# LED_DRIVER.net
KiCad netlist of a schematic drawn in EAGLE
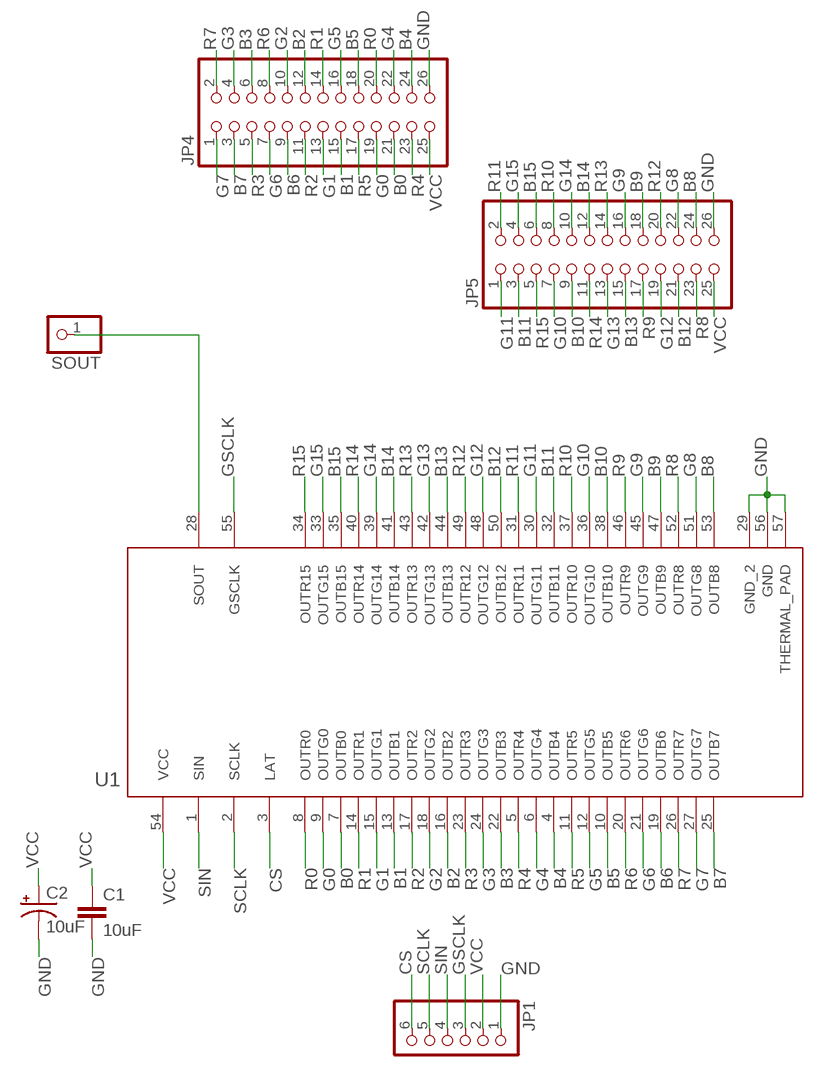
[diagram p0: schematic, sheet 1]

(export (version "E")
  (design (tool "Eeschema 10.0.6"))
  (components
    (comp (ref "C1")
      (value "10uF")
      (footprint "eagle-import:C0603")
      (libsource (lib "eagle-import") (part "C-EUC0603"))
    )
    (comp (ref "C2")
      (value "10uF")
      (footprint "eagle-import:E2-4")
      (libsource (lib "eagle-import") (part "CPOL-USE2-4"))
    )
    (comp (ref "JP1")
      (value "PINHD-1X6")
      (footprint "eagle-import:1X06")
      (libsource (lib "eagle-import") (part "PINHD-1X6"))
    )
    (comp (ref "JP4")
      (value "PINHD-2X13")
      (footprint "eagle-import:2X13")
      (libsource (lib "eagle-import") (part "PINHD-2X13"))
    )
    (comp (ref "JP5")
      (value "PINHD-2X13")
      (footprint "eagle-import:2X13")
      (libsource (lib "eagle-import") (part "PINHD-2X13"))
    )
    (comp (ref "SOUT")
      (value "PINHD-1X1")
      (footprint "eagle-import:1X01")
      (libsource (lib "eagle-import") (part "PINHD-1X1"))
    )
    (comp (ref "U1")
      (value "Value")
      (footprint "eagle-import:DCA0056F-IPC_B")
      (fields
        (field (name "MANUFACTURER") "Texas Instruments")
        (field (name "PARTNUMBER") "TLC6C5748QDCARQ1")
      )
      (libsource (lib "eagle-import") (part "TLC6C5748QDCARQ1DCA0056F-IPC_B"))
    )
  )
  (nets
    (net (code "1") (name "/B0") (class "Default")
      (node (ref "JP4") (pin "21") (pinfunction "21_21") (pintype "passive"))
      (node (ref "U1") (pin "7") (pinfunction "OUTB0_7") (pintype "output"))
    )
    (net (code "2") (name "/B1") (class "Default")
      (node (ref "JP4") (pin "15") (pinfunction "15_15") (pintype "passive"))
      (node (ref "U1") (pin "13") (pinfunction "OUTB1_13") (pintype "output"))
    )
    (net (code "3") (name "/B2") (class "Default")
      (node (ref "JP4") (pin "12") (pinfunction "12_12") (pintype "passive"))
      (node (ref "U1") (pin "16") (pinfunction "OUTB2_16") (pintype "output"))
    )
    (net (code "4") (name "/B3") (class "Default")
      (node (ref "JP4") (pin "6") (pinfunction "6_6") (pintype "passive"))
      (node (ref "U1") (pin "22") (pinfunction "OUTB3_22") (pintype "output"))
    )
    (net (code "5") (name "/B4") (class "Default")
      (node (ref "JP4") (pin "24") (pinfunction "24_24") (pintype "passive"))
      (node (ref "U1") (pin "4") (pinfunction "OUTB4_4") (pintype "output"))
    )
    (net (code "6") (name "/B5") (class "Default")
      (node (ref "JP4") (pin "18") (pinfunction "18_18") (pintype "passive"))
      (node (ref "U1") (pin "10") (pinfunction "OUTB5_10") (pintype "output"))
    )
    (net (code "7") (name "/B6") (class "Default")
      (node (ref "JP4") (pin "9") (pinfunction "9_9") (pintype "passive"))
      (node (ref "U1") (pin "19") (pinfunction "OUTB6_19") (pintype "output"))
    )
    (net (code "8") (name "/B7") (class "Default")
      (node (ref "JP4") (pin "3") (pinfunction "3_3") (pintype "passive"))
      (node (ref "U1") (pin "25") (pinfunction "OUTB7_25") (pintype "output"))
    )
    (net (code "9") (name "/B8") (class "Default")
      (node (ref "JP5") (pin "24") (pinfunction "24_24") (pintype "passive"))
      (node (ref "U1") (pin "53") (pinfunction "OUTB8_53") (pintype "output"))
    )
    (net (code "10") (name "/B9") (class "Default")
      (node (ref "JP5") (pin "18") (pinfunction "18_18") (pintype "passive"))
      (node (ref "U1") (pin "47") (pinfunction "OUTB9_47") (pintype "output"))
    )
    (net (code "11") (name "/B10") (class "Default")
      (node (ref "JP5") (pin "9") (pinfunction "9_9") (pintype "passive"))
      (node (ref "U1") (pin "38") (pinfunction "OUTB10_38") (pintype "output"))
    )
    (net (code "12") (name "/B11") (class "Default")
      (node (ref "JP5") (pin "3") (pinfunction "3_3") (pintype "passive"))
      (node (ref "U1") (pin "32") (pinfunction "OUTB11_32") (pintype "output"))
    )
    (net (code "13") (name "/B12") (class "Default")
      (node (ref "JP5") (pin "21") (pinfunction "21_21") (pintype "passive"))
      (node (ref "U1") (pin "50") (pinfunction "OUTB12_50") (pintype "output"))
    )
    (net (code "14") (name "/B13") (class "Default")
      (node (ref "JP5") (pin "15") (pinfunction "15_15") (pintype "passive"))
      (node (ref "U1") (pin "44") (pinfunction "OUTB13_44") (pintype "output"))
    )
    (net (code "15") (name "/B14") (class "Default")
      (node (ref "JP5") (pin "12") (pinfunction "12_12") (pintype "passive"))
      (node (ref "U1") (pin "41") (pinfunction "OUTB14_41") (pintype "output"))
    )
    (net (code "16") (name "/B15") (class "Default")
      (node (ref "JP5") (pin "6") (pinfunction "6_6") (pintype "passive"))
      (node (ref "U1") (pin "35") (pinfunction "OUTB15_35") (pintype "output"))
    )
    (net (code "17") (name "/CS") (class "Default")
      (node (ref "JP1") (pin "6") (pinfunction "6_6") (pintype "passive"))
      (node (ref "U1") (pin "3") (pinfunction "LAT_3") (pintype "input"))
    )
    (net (code "18") (name "/G0") (class "Default")
      (node (ref "JP4") (pin "19") (pinfunction "19_19") (pintype "passive"))
      (node (ref "U1") (pin "9") (pinfunction "OUTG0_9") (pintype "output"))
    )
    (net (code "19") (name "/G1") (class "Default")
      (node (ref "JP4") (pin "13") (pinfunction "13_13") (pintype "passive"))
      (node (ref "U1") (pin "15") (pinfunction "OUTG1_15") (pintype "output"))
    )
    (net (code "20") (name "/G2") (class "Default")
      (node (ref "JP4") (pin "10") (pinfunction "10_10") (pintype "passive"))
      (node (ref "U1") (pin "18") (pinfunction "OUTG2_18") (pintype "output"))
    )
    (net (code "21") (name "/G3") (class "Default")
      (node (ref "JP4") (pin "4") (pinfunction "4_4") (pintype "passive"))
      (node (ref "U1") (pin "24") (pinfunction "OUTG3_24") (pintype "output"))
    )
    (net (code "22") (name "/G4") (class "Default")
      (node (ref "JP4") (pin "22") (pinfunction "22_22") (pintype "passive"))
      (node (ref "U1") (pin "6") (pinfunction "OUTG4_6") (pintype "output"))
    )
    (net (code "23") (name "/G5") (class "Default")
      (node (ref "JP4") (pin "16") (pinfunction "16_16") (pintype "passive"))
      (node (ref "U1") (pin "12") (pinfunction "OUTG5_12") (pintype "output"))
    )
    (net (code "24") (name "/G6") (class "Default")
      (node (ref "JP4") (pin "7") (pinfunction "7_7") (pintype "passive"))
      (node (ref "U1") (pin "21") (pinfunction "OUTG6_21") (pintype "output"))
    )
    (net (code "25") (name "/G7") (class "Default")
      (node (ref "JP4") (pin "1") (pinfunction "1_1") (pintype "passive"))
      (node (ref "U1") (pin "27") (pinfunction "OUTG7_27") (pintype "output"))
    )
    (net (code "26") (name "/G8") (class "Default")
      (node (ref "JP5") (pin "22") (pinfunction "22_22") (pintype "passive"))
      (node (ref "U1") (pin "51") (pinfunction "OUTG8_51") (pintype "output"))
    )
    (net (code "27") (name "/G9") (class "Default")
      (node (ref "JP5") (pin "16") (pinfunction "16_16") (pintype "passive"))
      (node (ref "U1") (pin "45") (pinfunction "OUTG9_45") (pintype "output"))
    )
    (net (code "28") (name "/G10") (class "Default")
      (node (ref "JP5") (pin "7") (pinfunction "7_7") (pintype "passive"))
      (node (ref "U1") (pin "36") (pinfunction "OUTG10_36") (pintype "output"))
    )
    (net (code "29") (name "/G11") (class "Default")
      (node (ref "JP5") (pin "1") (pinfunction "1_1") (pintype "passive"))
      (node (ref "U1") (pin "30") (pinfunction "OUTG11_30") (pintype "output"))
    )
    (net (code "30") (name "/G12") (class "Default")
      (node (ref "JP5") (pin "19") (pinfunction "19_19") (pintype "passive"))
      (node (ref "U1") (pin "48") (pinfunction "OUTG12_48") (pintype "output"))
    )
    (net (code "31") (name "/G13") (class "Default")
      (node (ref "JP5") (pin "13") (pinfunction "13_13") (pintype "passive"))
      (node (ref "U1") (pin "42") (pinfunction "OUTG13_42") (pintype "output"))
    )
    (net (code "32") (name "/G14") (class "Default")
      (node (ref "JP5") (pin "10") (pinfunction "10_10") (pintype "passive"))
      (node (ref "U1") (pin "39") (pinfunction "OUTG14_39") (pintype "output"))
    )
    (net (code "33") (name "/G15") (class "Default")
      (node (ref "JP5") (pin "4") (pinfunction "4_4") (pintype "passive"))
      (node (ref "U1") (pin "33") (pinfunction "OUTG15_33") (pintype "output"))
    )
    (net (code "34") (name "/GND") (class "Default")
      (node (ref "C1") (pin "2") (pinfunction "2_2") (pintype "passive"))
      (node (ref "C2") (pin "-") (pinfunction "-_-") (pintype "passive"))
      (node (ref "JP1") (pin "1") (pinfunction "1_1") (pintype "passive"))
      (node (ref "JP4") (pin "26") (pinfunction "26_26") (pintype "passive"))
      (node (ref "JP5") (pin "26") (pinfunction "26_26") (pintype "passive"))
      (node (ref "U1") (pin "29") (pinfunction "GND_2_29") (pintype "power_in"))
      (node (ref "U1") (pin "56") (pinfunction "GND_56") (pintype "power_in"))
      (node (ref "U1") (pin "57") (pinfunction "THERMAL_PAD_57") (pintype "passive"))
    )
    (net (code "35") (name "/GSCLK") (class "Default")
      (node (ref "JP1") (pin "3") (pinfunction "3_3") (pintype "passive"))
      (node (ref "U1") (pin "55") (pinfunction "GSCLK_55") (pintype "input"))
    )
    (net (code "36") (name "/R0") (class "Default")
      (node (ref "JP4") (pin "20") (pinfunction "20_20") (pintype "passive"))
      (node (ref "U1") (pin "8") (pinfunction "OUTR0_8") (pintype "output"))
    )
    (net (code "37") (name "/R1") (class "Default")
      (node (ref "JP4") (pin "14") (pinfunction "14_14") (pintype "passive"))
      (node (ref "U1") (pin "14") (pinfunction "OUTR1_14") (pintype "output"))
    )
    (net (code "38") (name "/R2") (class "Default")
      (node (ref "JP4") (pin "11") (pinfunction "11_11") (pintype "passive"))
      (node (ref "U1") (pin "17") (pinfunction "OUTR2_17") (pintype "output"))
    )
    (net (code "39") (name "/R3") (class "Default")
      (node (ref "JP4") (pin "5") (pinfunction "5_5") (pintype "passive"))
      (node (ref "U1") (pin "23") (pinfunction "OUTR3_23") (pintype "output"))
    )
    (net (code "40") (name "/R4") (class "Default")
      (node (ref "JP4") (pin "23") (pinfunction "23_23") (pintype "passive"))
      (node (ref "U1") (pin "5") (pinfunction "OUTR4_5") (pintype "output"))
    )
    (net (code "41") (name "/R5") (class "Default")
      (node (ref "JP4") (pin "17") (pinfunction "17_17") (pintype "passive"))
      (node (ref "U1") (pin "11") (pinfunction "OUTR5_11") (pintype "output"))
    )
    (net (code "42") (name "/R6") (class "Default")
      (node (ref "JP4") (pin "8") (pinfunction "8_8") (pintype "passive"))
      (node (ref "U1") (pin "20") (pinfunction "OUTR6_20") (pintype "output"))
    )
    (net (code "43") (name "/R7") (class "Default")
      (node (ref "JP4") (pin "2") (pinfunction "2_2") (pintype "passive"))
      (node (ref "U1") (pin "26") (pinfunction "OUTR7_26") (pintype "output"))
    )
    (net (code "44") (name "/R8") (class "Default")
      (node (ref "JP5") (pin "23") (pinfunction "23_23") (pintype "passive"))
      (node (ref "U1") (pin "52") (pinfunction "OUTR8_52") (pintype "output"))
    )
    (net (code "45") (name "/R9") (class "Default")
      (node (ref "JP5") (pin "17") (pinfunction "17_17") (pintype "passive"))
      (node (ref "U1") (pin "46") (pinfunction "OUTR9_46") (pintype "output"))
    )
    (net (code "46") (name "/R10") (class "Default")
      (node (ref "JP5") (pin "8") (pinfunction "8_8") (pintype "passive"))
      (node (ref "U1") (pin "37") (pinfunction "OUTR10_37") (pintype "output"))
    )
    (net (code "47") (name "/R11") (class "Default")
      (node (ref "JP5") (pin "2") (pinfunction "2_2") (pintype "passive"))
      (node (ref "U1") (pin "31") (pinfunction "OUTR11_31") (pintype "output"))
    )
    (net (code "48") (name "/R12") (class "Default")
      (node (ref "JP5") (pin "20") (pinfunction "20_20") (pintype "passive"))
      (node (ref "U1") (pin "49") (pinfunction "OUTR12_49") (pintype "output"))
    )
    (net (code "49") (name "/R13") (class "Default")
      (node (ref "JP5") (pin "14") (pinfunction "14_14") (pintype "passive"))
      (node (ref "U1") (pin "43") (pinfunction "OUTR13_43") (pintype "output"))
    )
    (net (code "50") (name "/R14") (class "Default")
      (node (ref "JP5") (pin "11") (pinfunction "11_11") (pintype "passive"))
      (node (ref "U1") (pin "40") (pinfunction "OUTR14_40") (pintype "output"))
    )
    (net (code "51") (name "/R15") (class "Default")
      (node (ref "JP5") (pin "5") (pinfunction "5_5") (pintype "passive"))
      (node (ref "U1") (pin "34") (pinfunction "OUTR15_34") (pintype "output"))
    )
    (net (code "52") (name "/SCLK") (class "Default")
      (node (ref "JP1") (pin "5") (pinfunction "5_5") (pintype "passive"))
      (node (ref "U1") (pin "2") (pinfunction "SCLK_2") (pintype "input"))
    )
    (net (code "53") (name "/SIN") (class "Default")
      (node (ref "JP1") (pin "4") (pinfunction "4_4") (pintype "passive"))
      (node (ref "U1") (pin "1") (pinfunction "SIN_1") (pintype "input"))
    )
    (net (code "54") (name "/VCC") (class "Default")
      (node (ref "C1") (pin "1") (pinfunction "1_1") (pintype "passive"))
      (node (ref "C2") (pin "+") (pinfunction "+_+") (pintype "passive"))
      (node (ref "JP1") (pin "2") (pinfunction "2_2") (pintype "passive"))
      (node (ref "JP4") (pin "25") (pinfunction "25_25") (pintype "passive"))
      (node (ref "JP5") (pin "25") (pinfunction "25_25") (pintype "passive"))
      (node (ref "U1") (pin "54") (pinfunction "VCC_54") (pintype "power_in"))
    )
    (net (code "55") (name "Net-(U1-SOUT)") (class "Default")
      (node (ref "SOUT") (pin "1") (pinfunction "1_1") (pintype "passive"))
      (node (ref "U1") (pin "28") (pinfunction "SOUT_28") (pintype "output"))
    )
  )
)
